# 05-_MCU_POWER.net
KiCad netlist of a schematic drawn in Altium Designer
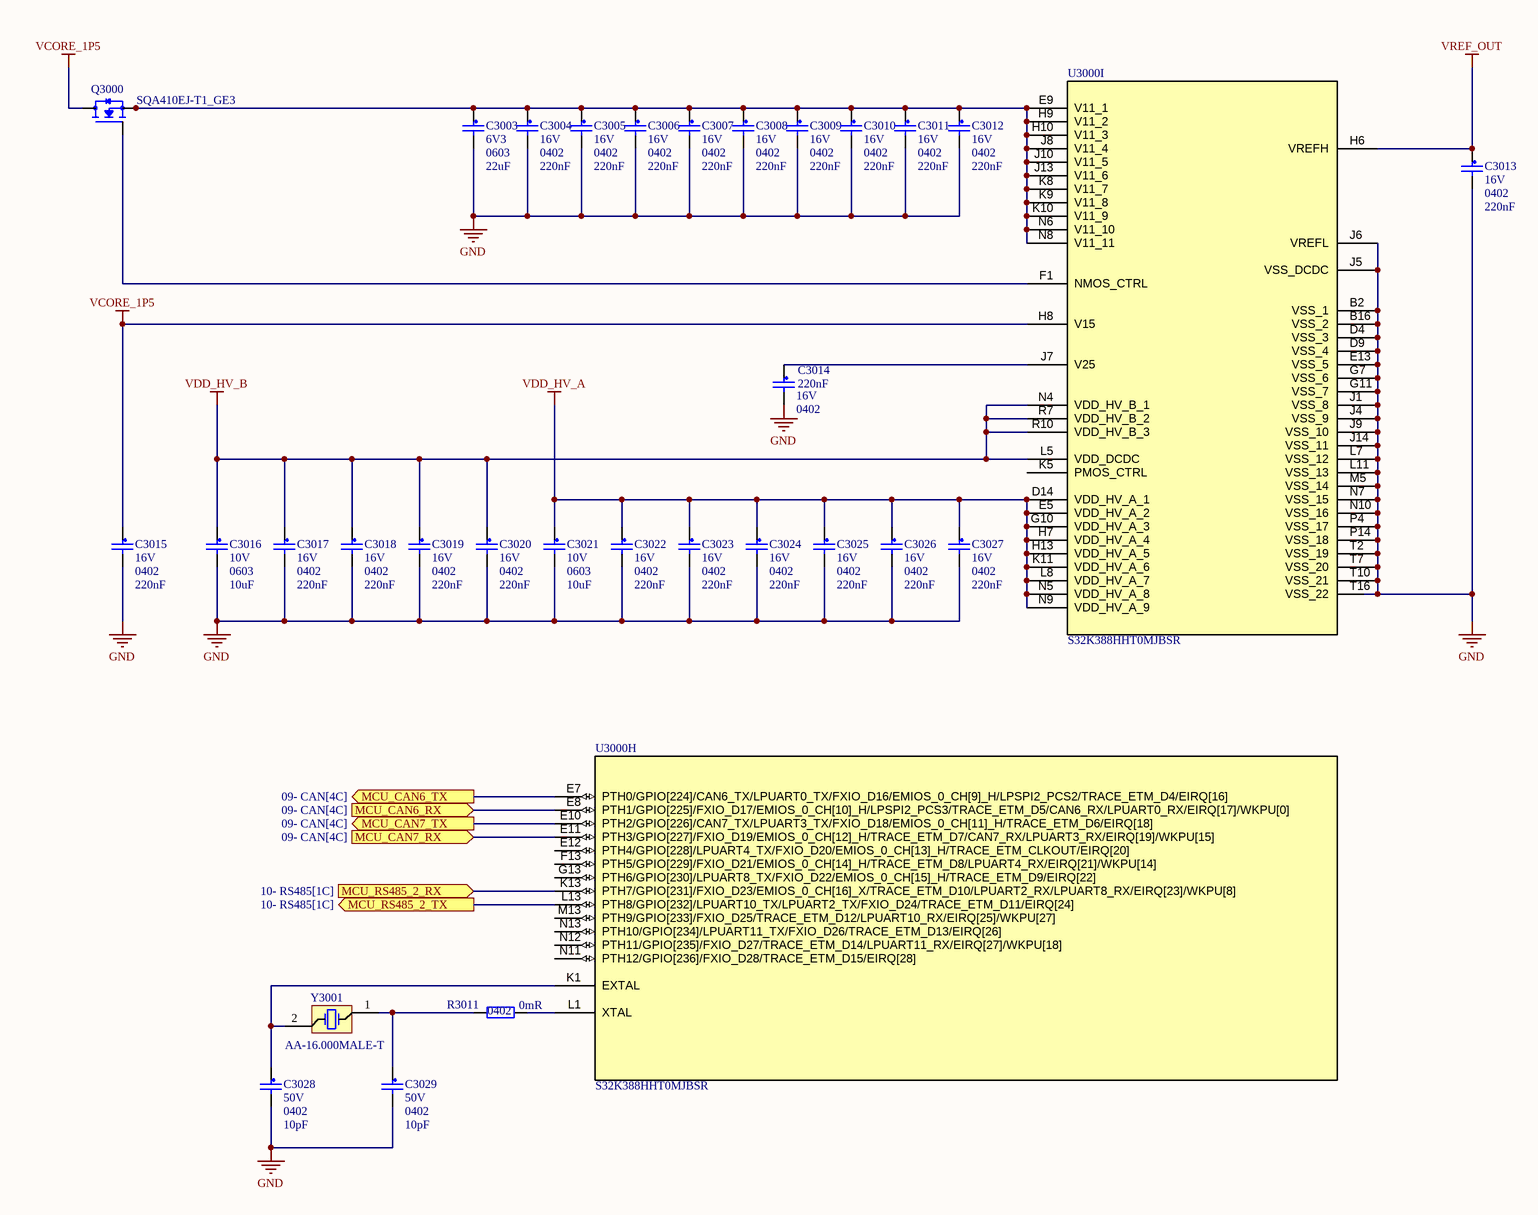
[diagram p0: 05- MCU POWER.SchDoc]

(export (version "E")
  (design (tool "Eeschema 10.0.6"))
  (components
    (comp (ref "C3003")
      (value "GRT188C80J226ME13D")
      (footprint "CAP0603")
      (description "CAP CER 22uF 6V3 20% X6S 0603 SMD")
      (fields
        (field (name "VOLTAGE RATING") "6V3")
        (field (name "CASE/PACKAGE") "0603")
        (field (name "CAPACITANCE") "22uF")
      )
      (libsource (lib "VMO_Lib") (part "CMP-00267-6"))
    )
    (comp (ref "C3004")
      (value "GCM155R71C224KE02D")
      (footprint "CAP0402")
      (description "CAP CER 0.22UF 16V X7R 0402")
      (fields
        (field (name "TOLERANCE") "10%")
        (field (name "VOLTAGE RATING") "16V")
        (field (name "CASE/PACKAGE") "0402")
        (field (name "CAPACITANCE") "220nF")
      )
      (libsource (lib "VMO_Lib") (part "CMP-00362-1"))
    )
    (comp (ref "C3005")
      (value "GCM155R71C224KE02D")
      (footprint "CAP0402")
      (description "CAP CER 0.22UF 16V X7R 0402")
      (fields
        (field (name "TOLERANCE") "10%")
        (field (name "VOLTAGE RATING") "16V")
        (field (name "CASE/PACKAGE") "0402")
        (field (name "CAPACITANCE") "220nF")
      )
      (libsource (lib "VMO_Lib") (part "CMP-00362-1"))
    )
    (comp (ref "C3006")
      (value "GCM155R71C224KE02D")
      (footprint "CAP0402")
      (description "CAP CER 0.22UF 16V X7R 0402")
      (fields
        (field (name "TOLERANCE") "10%")
        (field (name "VOLTAGE RATING") "16V")
        (field (name "CASE/PACKAGE") "0402")
        (field (name "CAPACITANCE") "220nF")
      )
      (libsource (lib "VMO_Lib") (part "CMP-00362-1"))
    )
    (comp (ref "C3007")
      (value "GCM155R71C224KE02D")
      (footprint "CAP0402")
      (description "CAP CER 0.22UF 16V X7R 0402")
      (fields
        (field (name "TOLERANCE") "10%")
        (field (name "VOLTAGE RATING") "16V")
        (field (name "CASE/PACKAGE") "0402")
        (field (name "CAPACITANCE") "220nF")
      )
      (libsource (lib "VMO_Lib") (part "CMP-00362-1"))
    )
    (comp (ref "C3008")
      (value "GCM155R71C224KE02D")
      (footprint "CAP0402")
      (description "CAP CER 0.22UF 16V X7R 0402")
      (fields
        (field (name "TOLERANCE") "10%")
        (field (name "VOLTAGE RATING") "16V")
        (field (name "CASE/PACKAGE") "0402")
        (field (name "CAPACITANCE") "220nF")
      )
      (libsource (lib "VMO_Lib") (part "CMP-00362-1"))
    )
    (comp (ref "C3009")
      (value "GCM155R71C224KE02D")
      (footprint "CAP0402")
      (description "CAP CER 0.22UF 16V X7R 0402")
      (fields
        (field (name "TOLERANCE") "10%")
        (field (name "VOLTAGE RATING") "16V")
        (field (name "CASE/PACKAGE") "0402")
        (field (name "CAPACITANCE") "220nF")
      )
      (libsource (lib "VMO_Lib") (part "CMP-00362-1"))
    )
    (comp (ref "C3010")
      (value "GCM155R71C224KE02D")
      (footprint "CAP0402")
      (description "CAP CER 0.22UF 16V X7R 0402")
      (fields
        (field (name "TOLERANCE") "10%")
        (field (name "VOLTAGE RATING") "16V")
        (field (name "CASE/PACKAGE") "0402")
        (field (name "CAPACITANCE") "220nF")
      )
      (libsource (lib "VMO_Lib") (part "CMP-00362-1"))
    )
    (comp (ref "C3011")
      (value "GCM155R71C224KE02D")
      (footprint "CAP0402")
      (description "CAP CER 0.22UF 16V X7R 0402")
      (fields
        (field (name "TOLERANCE") "10%")
        (field (name "VOLTAGE RATING") "16V")
        (field (name "CASE/PACKAGE") "0402")
        (field (name "CAPACITANCE") "220nF")
      )
      (libsource (lib "VMO_Lib") (part "CMP-00362-1"))
    )
    (comp (ref "C3012")
      (value "GCM155R71C224KE02D")
      (footprint "CAP0402")
      (description "CAP CER 0.22UF 16V X7R 0402")
      (fields
        (field (name "TOLERANCE") "10%")
        (field (name "VOLTAGE RATING") "16V")
        (field (name "CASE/PACKAGE") "0402")
        (field (name "CAPACITANCE") "220nF")
      )
      (libsource (lib "VMO_Lib") (part "CMP-00362-1"))
    )
    (comp (ref "C3013")
      (value "GCM155R71C224KE02D")
      (footprint "CAP0402")
      (description "CAP CER 0.22UF 16V X7R 0402")
      (fields
        (field (name "TOLERANCE") "10%")
        (field (name "VOLTAGE RATING") "16V")
        (field (name "CASE/PACKAGE") "0402")
        (field (name "CAPACITANCE") "220nF")
      )
      (libsource (lib "VMO_Lib") (part "CMP-00362-1"))
    )
    (comp (ref "C3014")
      (value "GCM155R71C224KE02D")
      (footprint "CAP0402")
      (description "CAP CER 0.22UF 16V X7R 0402")
      (fields
        (field (name "TOLERANCE") "10%")
        (field (name "VOLTAGE RATING") "16V")
        (field (name "CASE/PACKAGE") "0402")
        (field (name "CAPACITANCE") "220nF")
      )
      (libsource (lib "VMO_Lib") (part "CMP-00362-1"))
    )
    (comp (ref "C3015")
      (value "GCM155R71C224KE02D")
      (footprint "CAP0402")
      (description "CAP CER 0.22UF 16V X7R 0402")
      (fields
        (field (name "TOLERANCE") "10%")
        (field (name "VOLTAGE RATING") "16V")
        (field (name "CASE/PACKAGE") "0402")
        (field (name "CAPACITANCE") "220nF")
      )
      (libsource (lib "VMO_Lib") (part "CMP-00362-1"))
    )
    (comp (ref "C3016")
      (value "CL10A106MP8NNNC")
      (footprint "CAP0603")
      (description "CAP CER 10uF 10V X5R 0603")
      (fields
        (field (name "TOLERANCE") "20%")
        (field (name "VOLTAGE RATING") "10V")
        (field (name "CASE/PACKAGE") "0603")
        (field (name "CAPACITANCE") "10uF")
      )
      (libsource (lib "VMO_Lib") (part "CMP-ROOT-0115-5"))
    )
    (comp (ref "C3017")
      (value "GCM155R71C224KE02D")
      (footprint "CAP0402")
      (description "CAP CER 0.22UF 16V X7R 0402")
      (fields
        (field (name "TOLERANCE") "10%")
        (field (name "VOLTAGE RATING") "16V")
        (field (name "CASE/PACKAGE") "0402")
        (field (name "CAPACITANCE") "220nF")
      )
      (libsource (lib "VMO_Lib") (part "CMP-00362-1"))
    )
    (comp (ref "C3018")
      (value "GCM155R71C224KE02D")
      (footprint "CAP0402")
      (description "CAP CER 0.22UF 16V X7R 0402")
      (fields
        (field (name "TOLERANCE") "10%")
        (field (name "VOLTAGE RATING") "16V")
        (field (name "CASE/PACKAGE") "0402")
        (field (name "CAPACITANCE") "220nF")
      )
      (libsource (lib "VMO_Lib") (part "CMP-00362-1"))
    )
    (comp (ref "C3019")
      (value "GCM155R71C224KE02D")
      (footprint "CAP0402")
      (description "CAP CER 0.22UF 16V X7R 0402")
      (fields
        (field (name "TOLERANCE") "10%")
        (field (name "VOLTAGE RATING") "16V")
        (field (name "CASE/PACKAGE") "0402")
        (field (name "CAPACITANCE") "220nF")
      )
      (libsource (lib "VMO_Lib") (part "CMP-00362-1"))
    )
    (comp (ref "C3020")
      (value "GCM155R71C224KE02D")
      (footprint "CAP0402")
      (description "CAP CER 0.22UF 16V X7R 0402")
      (fields
        (field (name "TOLERANCE") "10%")
        (field (name "VOLTAGE RATING") "16V")
        (field (name "CASE/PACKAGE") "0402")
        (field (name "CAPACITANCE") "220nF")
      )
      (libsource (lib "VMO_Lib") (part "CMP-00362-1"))
    )
    (comp (ref "C3021")
      (value "CL10A106MP8NNNC")
      (footprint "CAP0603")
      (description "CAP CER 10uF 10V X5R 0603")
      (fields
        (field (name "TOLERANCE") "20%")
        (field (name "VOLTAGE RATING") "10V")
        (field (name "CASE/PACKAGE") "0603")
        (field (name "CAPACITANCE") "10uF")
      )
      (libsource (lib "VMO_Lib") (part "CMP-ROOT-0115-5"))
    )
    (comp (ref "C3022")
      (value "GCM155R71C224KE02D")
      (footprint "CAP0402")
      (description "CAP CER 0.22UF 16V X7R 0402")
      (fields
        (field (name "TOLERANCE") "10%")
        (field (name "VOLTAGE RATING") "16V")
        (field (name "CASE/PACKAGE") "0402")
        (field (name "CAPACITANCE") "220nF")
      )
      (libsource (lib "VMO_Lib") (part "CMP-00362-1"))
    )
    (comp (ref "C3023")
      (value "GCM155R71C224KE02D")
      (footprint "CAP0402")
      (description "CAP CER 0.22UF 16V X7R 0402")
      (fields
        (field (name "TOLERANCE") "10%")
        (field (name "VOLTAGE RATING") "16V")
        (field (name "CASE/PACKAGE") "0402")
        (field (name "CAPACITANCE") "220nF")
      )
      (libsource (lib "VMO_Lib") (part "CMP-00362-1"))
    )
    (comp (ref "C3024")
      (value "GCM155R71C224KE02D")
      (footprint "CAP0402")
      (description "CAP CER 0.22UF 16V X7R 0402")
      (fields
        (field (name "TOLERANCE") "10%")
        (field (name "VOLTAGE RATING") "16V")
        (field (name "CASE/PACKAGE") "0402")
        (field (name "CAPACITANCE") "220nF")
      )
      (libsource (lib "VMO_Lib") (part "CMP-00362-1"))
    )
    (comp (ref "C3025")
      (value "GCM155R71C224KE02D")
      (footprint "CAP0402")
      (description "CAP CER 0.22UF 16V X7R 0402")
      (fields
        (field (name "TOLERANCE") "10%")
        (field (name "VOLTAGE RATING") "16V")
        (field (name "CASE/PACKAGE") "0402")
        (field (name "CAPACITANCE") "220nF")
      )
      (libsource (lib "VMO_Lib") (part "CMP-00362-1"))
    )
    (comp (ref "C3026")
      (value "GCM155R71C224KE02D")
      (footprint "CAP0402")
      (description "CAP CER 0.22UF 16V X7R 0402")
      (fields
        (field (name "TOLERANCE") "10%")
        (field (name "VOLTAGE RATING") "16V")
        (field (name "CASE/PACKAGE") "0402")
        (field (name "CAPACITANCE") "220nF")
      )
      (libsource (lib "VMO_Lib") (part "CMP-00362-1"))
    )
    (comp (ref "C3027")
      (value "GCM155R71C224KE02D")
      (footprint "CAP0402")
      (description "CAP CER 0.22UF 16V X7R 0402")
      (fields
        (field (name "TOLERANCE") "10%")
        (field (name "VOLTAGE RATING") "16V")
        (field (name "CASE/PACKAGE") "0402")
        (field (name "CAPACITANCE") "220nF")
      )
      (libsource (lib "VMO_Lib") (part "CMP-00362-1"))
    )
    (comp (ref "C3028")
      (value "GCM1555C1H100JA16D")
      (footprint "CAP0402")
      (description "CAP CER 10pF 50V 5% C0G 0402 SMD")
      (fields
        (field (name "TOLERANCE") "5%")
        (field (name "VOLTAGE RATING") "50V")
        (field (name "CASE/PACKAGE") "0402")
        (field (name "CAPACITANCE") "10pF")
      )
      (libsource (lib "VMO_Lib") (part "CMP-00258-4"))
    )
    (comp (ref "C3029")
      (value "GCM1555C1H100JA16D")
      (footprint "CAP0402")
      (description "CAP CER 10pF 50V 5% C0G 0402 SMD")
      (fields
        (field (name "TOLERANCE") "5%")
        (field (name "VOLTAGE RATING") "50V")
        (field (name "CASE/PACKAGE") "0402")
        (field (name "CAPACITANCE") "10pF")
      )
      (libsource (lib "VMO_Lib") (part "CMP-00258-4"))
    )
    (comp (ref "Q3000")
      (value "SQA410EJ-T1_GE3")
      (footprint "PowerPAK® SC-70-6")
      (description "MOSFET N-CH 20V 7.8A PPAK SC70-6")
      (fields
        (field (name "MANUFACTURER") "Vishay")
        (field (name "MANUFACTURER PART NUMBER") "SQA410EJ-T1-GE3")
      )
      (libsource (lib "VMO_Lib") (part "CMP-01172-1"))
    )
    (comp (ref "R3011")
      (value "RMCF0402ZT0R00")
      (footprint "RES0402")
      (description "RES 0R 1/16W 1% 0402 SMD")
      (fields (field (name "RESISTANCE") "0mR") (field (name "CASE/PACKAGE") "0402"))
      (libsource (lib "VMO_Lib") (part "CMP-ROOT-0037-10"))
    )
    (comp (ref "U3000")
      (value "S32K388HHT0MJBSR")
      (footprint "BGA289C80P17X17_1400X1400X152")
      (fields (field (name "MANUFACTURER") "NXP Semiconductors"))
      (libsource (lib "VMO_Lib") (part "CMP-01150-1"))
    )
    (comp (ref "Y3001")
      (value "AA-16.000MALE-T")
      (footprint "CRYSTAL5032")
      (description "CRYSTAL 16.0000MHZ 12PF SMD")
      (fields (field (name "MANUFACTURER") "TXC") (field (name "TOLERANCE") "0.003%"))
      (libsource (lib "VMO_Lib") (part "CMP-01173-1"))
    )
  )
  (nets
    (net (code "1") (name "/MCU_CAN6_RX") (class "Default")
      (node (ref "U3000") (pin "E8") (pinfunction "PTH1/GPIO[225]/FXIO_D17/EMIOS_0_CH[10]_H/LPSPI2_PCS3/TRACE_ETM_D5/CAN6_RX/LPUART0_RX/EIRQ[17]/WKPU[0]_E8") (pintype "bidirectional"))
    )
    (net (code "2") (name "/MCU_CAN6_TX") (class "Default")
      (node (ref "U3000") (pin "E7") (pinfunction "PTH0/GPIO[224]/CAN6_TX/LPUART0_TX/FXIO_D16/EMIOS_0_CH[9]_H/LPSPI2_PCS2/TRACE_ETM_D4/EIRQ[16]_E7") (pintype "bidirectional"))
    )
    (net (code "3") (name "/MCU_CAN7_RX") (class "Default")
      (node (ref "U3000") (pin "E11") (pinfunction "PTH3/GPIO[227]/FXIO_D19/EMIOS_0_CH[12]_H/TRACE_ETM_D7/CAN7_RX/LPUART3_RX/EIRQ[19]/WKPU[15]_E11") (pintype "bidirectional"))
    )
    (net (code "4") (name "/MCU_CAN7_TX") (class "Default")
      (node (ref "U3000") (pin "E10") (pinfunction "PTH2/GPIO[226]/CAN7_TX/LPUART3_TX/FXIO_D18/EMIOS_0_CH[11]_H/TRACE_ETM_D6/EIRQ[18]_E10") (pintype "bidirectional"))
    )
    (net (code "5") (name "/MCU_RS485_2_RX") (class "Default")
      (node (ref "U3000") (pin "K13") (pinfunction "PTH7/GPIO[231]/FXIO_D23/EMIOS_0_CH[16]_X/TRACE_ETM_D10/LPUART2_RX/LPUART8_RX/EIRQ[23]/WKPU[8]_K13") (pintype "bidirectional"))
    )
    (net (code "6") (name "/MCU_RS485_2_TX") (class "Default")
      (node (ref "U3000") (pin "L13") (pinfunction "PTH8/GPIO[232]/LPUART10_TX/LPUART2_TX/FXIO_D24/TRACE_ETM_D11/EIRQ[24]_L13") (pintype "bidirectional"))
    )
    (net (code "7") (name "GND") (class "Default")
      (node (ref "C3003") (pin "2") (pinfunction "2_2") (pintype "passive"))
      (node (ref "C3004") (pin "2") (pinfunction "2_2") (pintype "passive"))
      (node (ref "C3005") (pin "2") (pinfunction "2_2") (pintype "passive"))
      (node (ref "C3006") (pin "2") (pinfunction "2_2") (pintype "passive"))
      (node (ref "C3007") (pin "2") (pinfunction "2_2") (pintype "passive"))
      (node (ref "C3008") (pin "2") (pinfunction "2_2") (pintype "passive"))
      (node (ref "C3009") (pin "2") (pinfunction "2_2") (pintype "passive"))
      (node (ref "C3010") (pin "2") (pinfunction "2_2") (pintype "passive"))
      (node (ref "C3011") (pin "2") (pinfunction "2_2") (pintype "passive"))
      (node (ref "C3012") (pin "2") (pinfunction "2_2") (pintype "passive"))
      (node (ref "C3013") (pin "2") (pinfunction "2_2") (pintype "passive"))
      (node (ref "C3014") (pin "2") (pinfunction "2_2") (pintype "passive"))
      (node (ref "C3015") (pin "2") (pinfunction "2_2") (pintype "passive"))
      (node (ref "C3016") (pin "2") (pinfunction "2_2") (pintype "passive"))
      (node (ref "C3017") (pin "2") (pinfunction "2_2") (pintype "passive"))
      (node (ref "C3018") (pin "2") (pinfunction "2_2") (pintype "passive"))
      (node (ref "C3019") (pin "2") (pinfunction "2_2") (pintype "passive"))
      (node (ref "C3020") (pin "2") (pinfunction "2_2") (pintype "passive"))
      (node (ref "C3021") (pin "2") (pinfunction "2_2") (pintype "passive"))
      (node (ref "C3022") (pin "2") (pinfunction "2_2") (pintype "passive"))
      (node (ref "C3023") (pin "2") (pinfunction "2_2") (pintype "passive"))
      (node (ref "C3024") (pin "2") (pinfunction "2_2") (pintype "passive"))
      (node (ref "C3025") (pin "2") (pinfunction "2_2") (pintype "passive"))
      (node (ref "C3026") (pin "2") (pinfunction "2_2") (pintype "passive"))
      (node (ref "C3027") (pin "2") (pinfunction "2_2") (pintype "passive"))
      (node (ref "C3028") (pin "2") (pinfunction "2_2") (pintype "passive"))
      (node (ref "C3029") (pin "2") (pinfunction "2_2") (pintype "passive"))
      (node (ref "U3000") (pin "B16") (pinfunction "VSS_2_B16") (pintype "passive"))
      (node (ref "U3000") (pin "B2") (pinfunction "VSS_1_B2") (pintype "passive"))
      (node (ref "U3000") (pin "D4") (pinfunction "VSS_3_D4") (pintype "passive"))
      (node (ref "U3000") (pin "D9") (pinfunction "VSS_4_D9") (pintype "passive"))
      (node (ref "U3000") (pin "E13") (pinfunction "VSS_5_E13") (pintype "passive"))
      (node (ref "U3000") (pin "G11") (pinfunction "VSS_7_G11") (pintype "passive"))
      (node (ref "U3000") (pin "G7") (pinfunction "VSS_6_G7") (pintype "passive"))
      (node (ref "U3000") (pin "J1") (pinfunction "VSS_8_J1") (pintype "passive"))
      (node (ref "U3000") (pin "J14") (pinfunction "VSS_11_J14") (pintype "passive"))
      (node (ref "U3000") (pin "J4") (pinfunction "VSS_9_J4") (pintype "passive"))
      (node (ref "U3000") (pin "J5") (pinfunction "VSS_DCDC_J5") (pintype "passive"))
      (node (ref "U3000") (pin "J6") (pinfunction "VREFL_J6") (pintype "passive"))
      (node (ref "U3000") (pin "J9") (pinfunction "VSS_10_J9") (pintype "passive"))
      (node (ref "U3000") (pin "L11") (pinfunction "VSS_13_L11") (pintype "passive"))
      (node (ref "U3000") (pin "L7") (pinfunction "VSS_12_L7") (pintype "passive"))
      (node (ref "U3000") (pin "M5") (pinfunction "VSS_14_M5") (pintype "passive"))
      (node (ref "U3000") (pin "N10") (pinfunction "VSS_16_N10") (pintype "passive"))
      (node (ref "U3000") (pin "N7") (pinfunction "VSS_15_N7") (pintype "passive"))
      (node (ref "U3000") (pin "P14") (pinfunction "VSS_18_P14") (pintype "passive"))
      (node (ref "U3000") (pin "P4") (pinfunction "VSS_17_P4") (pintype "passive"))
      (node (ref "U3000") (pin "T10") (pinfunction "VSS_21_T10") (pintype "passive"))
      (node (ref "U3000") (pin "T16") (pinfunction "VSS_22_T16") (pintype "passive"))
      (node (ref "U3000") (pin "T2") (pinfunction "VSS_19_T2") (pintype "passive"))
      (node (ref "U3000") (pin "T7") (pinfunction "VSS_20_T7") (pintype "passive"))
    )
    (net (code "8") (name "Net-(Q3000-G)") (class "Default")
      (node (ref "Q3000") (pin "3") (pinfunction "G_3") (pintype "passive"))
      (node (ref "U3000") (pin "F1") (pinfunction "NMOS_CTRL_F1") (pintype "passive"))
    )
    (net (code "9") (name "Net-(U3000H-EXTAL)") (class "Default")
      (node (ref "C3028") (pin "1") (pinfunction "1_1") (pintype "passive"))
      (node (ref "U3000") (pin "K1") (pinfunction "EXTAL_K1") (pintype "passive"))
      (node (ref "Y3001") (pin "2") (pinfunction "OSC2_2") (pintype "passive"))
    )
    (net (code "10") (name "Net-(U3000H-XTAL)") (class "Default")
      (node (ref "R3011") (pin "2") (pinfunction "2_2") (pintype "passive"))
      (node (ref "U3000") (pin "L1") (pinfunction "XTAL_L1") (pintype "passive"))
    )
    (net (code "11") (name "Net-(U3000I-V11_1)") (class "Default")
      (node (ref "C3003") (pin "1") (pinfunction "1_1") (pintype "passive"))
      (node (ref "C3004") (pin "1") (pinfunction "1_1") (pintype "passive"))
      (node (ref "C3005") (pin "1") (pinfunction "1_1") (pintype "passive"))
      (node (ref "C3006") (pin "1") (pinfunction "1_1") (pintype "passive"))
      (node (ref "C3007") (pin "1") (pinfunction "1_1") (pintype "passive"))
      (node (ref "C3008") (pin "1") (pinfunction "1_1") (pintype "passive"))
      (node (ref "C3009") (pin "1") (pinfunction "1_1") (pintype "passive"))
      (node (ref "C3010") (pin "1") (pinfunction "1_1") (pintype "passive"))
      (node (ref "C3011") (pin "1") (pinfunction "1_1") (pintype "passive"))
      (node (ref "C3012") (pin "1") (pinfunction "1_1") (pintype "passive"))
      (node (ref "Q3000") (pin "4") (pinfunction "S_4") (pintype "passive"))
      (node (ref "Q3000") (pin "7") (pinfunction "S_7") (pintype "passive"))
      (node (ref "U3000") (pin "E9") (pinfunction "V11_1_E9") (pintype "passive"))
      (node (ref "U3000") (pin "H10") (pinfunction "V11_3_H10") (pintype "passive"))
      (node (ref "U3000") (pin "H9") (pinfunction "V11_2_H9") (pintype "passive"))
      (node (ref "U3000") (pin "J10") (pinfunction "V11_5_J10") (pintype "passive"))
      (node (ref "U3000") (pin "J13") (pinfunction "V11_6_J13") (pintype "passive"))
      (node (ref "U3000") (pin "J8") (pinfunction "V11_4_J8") (pintype "passive"))
      (node (ref "U3000") (pin "K10") (pinfunction "V11_9_K10") (pintype "passive"))
      (node (ref "U3000") (pin "K8") (pinfunction "V11_7_K8") (pintype "passive"))
      (node (ref "U3000") (pin "K9") (pinfunction "V11_8_K9") (pintype "passive"))
      (node (ref "U3000") (pin "N6") (pinfunction "V11_10_N6") (pintype "passive"))
      (node (ref "U3000") (pin "N8") (pinfunction "V11_11_N8") (pintype "passive"))
    )
    (net (code "12") (name "Net-(U3000I-V25)") (class "Default")
      (node (ref "C3014") (pin "1") (pinfunction "1_1") (pintype "passive"))
      (node (ref "U3000") (pin "J7") (pinfunction "V25_J7") (pintype "passive"))
    )
    (net (code "13") (name "Net-(Y3001-OSC1)") (class "Default")
      (node (ref "C3029") (pin "1") (pinfunction "1_1") (pintype "passive"))
      (node (ref "R3011") (pin "1") (pinfunction "1_1") (pintype "passive"))
      (node (ref "Y3001") (pin "1") (pinfunction "OSC1_1") (pintype "passive"))
    )
    (net (code "14") (name "VCORE_1P5") (class "Default")
      (node (ref "C3015") (pin "1") (pinfunction "1_1") (pintype "passive"))
      (node (ref "Q3000") (pin "1_2_5_6") (pinfunction "D_1_2_5_6") (pintype "passive"))
      (node (ref "U3000") (pin "H8") (pinfunction "V15_H8") (pintype "passive"))
    )
    (net (code "15") (name "VDD_HV_A") (class "Default")
      (node (ref "C3021") (pin "1") (pinfunction "1_1") (pintype "passive"))
      (node (ref "C3022") (pin "1") (pinfunction "1_1") (pintype "passive"))
      (node (ref "C3023") (pin "1") (pinfunction "1_1") (pintype "passive"))
      (node (ref "C3024") (pin "1") (pinfunction "1_1") (pintype "passive"))
      (node (ref "C3025") (pin "1") (pinfunction "1_1") (pintype "passive"))
      (node (ref "C3026") (pin "1") (pinfunction "1_1") (pintype "passive"))
      (node (ref "C3027") (pin "1") (pinfunction "1_1") (pintype "passive"))
      (node (ref "U3000") (pin "D14") (pinfunction "VDD_HV_A_1_D14") (pintype "passive"))
      (node (ref "U3000") (pin "E5") (pinfunction "VDD_HV_A_2_E5") (pintype "passive"))
      (node (ref "U3000") (pin "G10") (pinfunction "VDD_HV_A_3_G10") (pintype "passive"))
      (node (ref "U3000") (pin "H13") (pinfunction "VDD_HV_A_5_H13") (pintype "passive"))
      (node (ref "U3000") (pin "H7") (pinfunction "VDD_HV_A_4_H7") (pintype "passive"))
      (node (ref "U3000") (pin "K11") (pinfunction "VDD_HV_A_6_K11") (pintype "passive"))
      (node (ref "U3000") (pin "L8") (pinfunction "VDD_HV_A_7_L8") (pintype "passive"))
      (node (ref "U3000") (pin "N5") (pinfunction "VDD_HV_A_8_N5") (pintype "passive"))
      (node (ref "U3000") (pin "N9") (pinfunction "VDD_HV_A_9_N9") (pintype "passive"))
    )
    (net (code "16") (name "VDD_HV_B") (class "Default")
      (node (ref "C3016") (pin "1") (pinfunction "1_1") (pintype "passive"))
      (node (ref "C3017") (pin "1") (pinfunction "1_1") (pintype "passive"))
      (node (ref "C3018") (pin "1") (pinfunction "1_1") (pintype "passive"))
      (node (ref "C3019") (pin "1") (pinfunction "1_1") (pintype "passive"))
      (node (ref "C3020") (pin "1") (pinfunction "1_1") (pintype "passive"))
      (node (ref "U3000") (pin "L5") (pinfunction "VDD_DCDC_L5") (pintype "passive"))
      (node (ref "U3000") (pin "N4") (pinfunction "VDD_HV_B_1_N4") (pintype "passive"))
      (node (ref "U3000") (pin "R10") (pinfunction "VDD_HV_B_3_R10") (pintype "passive"))
      (node (ref "U3000") (pin "R7") (pinfunction "VDD_HV_B_2_R7") (pintype "passive"))
    )
    (net (code "17") (name "VREF_OUT") (class "Default")
      (node (ref "C3013") (pin "1") (pinfunction "1_1") (pintype "passive"))
      (node (ref "U3000") (pin "H6") (pinfunction "VREFH_H6") (pintype "passive"))
    )
    (net (code "18") (name "unconnected-(U3000H-PTH4{slash}GPIO[228]{slash}LPUART4_TX{slash}FXIO_D20{slash}EMIOS_0_CH[13]_H{slash}TRACE_ETM_CLKOUT{slash}EIRQ[20]-PadE12)") (class "Default")
      (node (ref "U3000") (pin "E12") (pinfunction "PTH4/GPIO[228]/LPUART4_TX/FXIO_D20/EMIOS_0_CH[13]_H/TRACE_ETM_CLKOUT/EIRQ[20]_E12") (pintype "bidirectional"))
    )
    (net (code "19") (name "unconnected-(U3000H-PTH5{slash}GPIO[229]{slash}FXIO_D21{slash}EMIOS_0_CH[14]_H{slash}TRACE_ETM_D8{slash}LPUART4_RX{slash}EIRQ[21]{slash}WKPU[14]-PadF13)") (class "Default")
      (node (ref "U3000") (pin "F13") (pinfunction "PTH5/GPIO[229]/FXIO_D21/EMIOS_0_CH[14]_H/TRACE_ETM_D8/LPUART4_RX/EIRQ[21]/WKPU[14]_F13") (pintype "bidirectional"))
    )
    (net (code "20") (name "unconnected-(U3000H-PTH6{slash}GPIO[230]{slash}LPUART8_TX{slash}FXIO_D22{slash}EMIOS_0_CH[15]_H{slash}TRACE_ETM_D9{slash}EIRQ[22]-PadG13)") (class "Default")
      (node (ref "U3000") (pin "G13") (pinfunction "PTH6/GPIO[230]/LPUART8_TX/FXIO_D22/EMIOS_0_CH[15]_H/TRACE_ETM_D9/EIRQ[22]_G13") (pintype "bidirectional"))
    )
    (net (code "21") (name "unconnected-(U3000H-PTH9{slash}GPIO[233]{slash}FXIO_D25{slash}TRACE_ETM_D12{slash}LPUART10_RX{slash}EIRQ[25]{slash}WKPU[27]-PadM13)") (class "Default")
      (node (ref "U3000") (pin "M13") (pinfunction "PTH9/GPIO[233]/FXIO_D25/TRACE_ETM_D12/LPUART10_RX/EIRQ[25]/WKPU[27]_M13") (pintype "bidirectional"))
    )
    (net (code "22") (name "unconnected-(U3000H-PTH10{slash}GPIO[234]{slash}LPUART11_TX{slash}FXIO_D26{slash}TRACE_ETM_D13{slash}EIRQ[26]-PadN13)") (class "Default")
      (node (ref "U3000") (pin "N13") (pinfunction "PTH10/GPIO[234]/LPUART11_TX/FXIO_D26/TRACE_ETM_D13/EIRQ[26]_N13") (pintype "bidirectional"))
    )
    (net (code "23") (name "unconnected-(U3000H-PTH11{slash}GPIO[235]{slash}FXIO_D27{slash}TRACE_ETM_D14{slash}LPUART11_RX{slash}EIRQ[27]{slash}WKPU[18]-PadN12)") (class "Default")
      (node (ref "U3000") (pin "N12") (pinfunction "PTH11/GPIO[235]/FXIO_D27/TRACE_ETM_D14/LPUART11_RX/EIRQ[27]/WKPU[18]_N12") (pintype "bidirectional"))
    )
    (net (code "24") (name "unconnected-(U3000H-PTH12{slash}GPIO[236]{slash}FXIO_D28{slash}TRACE_ETM_D15{slash}EIRQ[28]-PadN11)") (class "Default")
      (node (ref "U3000") (pin "N11") (pinfunction "PTH12/GPIO[236]/FXIO_D28/TRACE_ETM_D15/EIRQ[28]_N11") (pintype "bidirectional"))
    )
    (net (code "25") (name "unconnected-(U3000I-PMOS_CTRL-PadK5)") (class "Default")
      (node (ref "U3000") (pin "K5") (pinfunction "PMOS_CTRL_K5") (pintype "passive"))
    )
  )
)
